# SwitchBoard_1_1.net
KiCad netlist of a schematic drawn in EAGLE
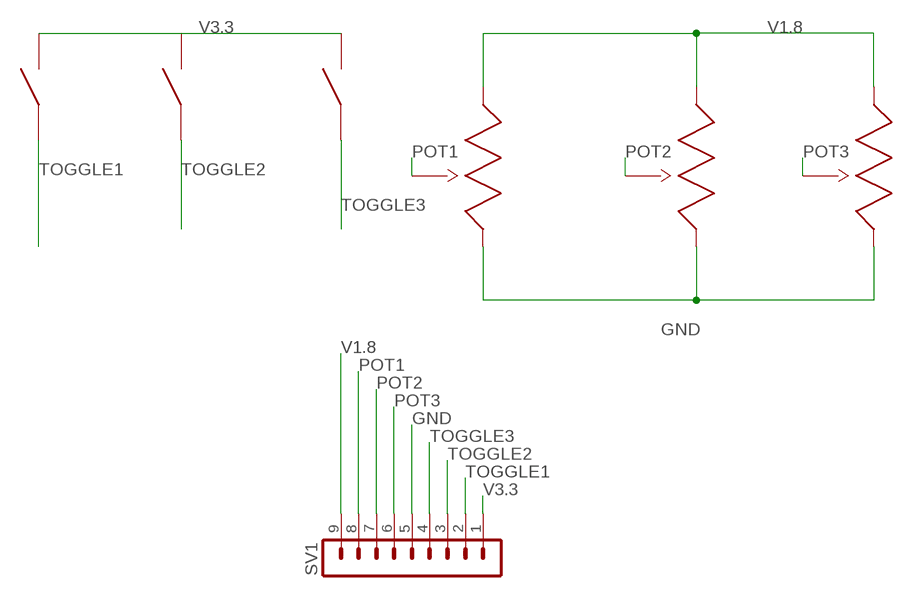
[diagram p0: schematic, sheet 1]

(export (version "E")
  (design (tool "Eeschema 10.0.6"))
  (components
    (comp (ref "POT1")
      (value "PRS11S-11")
      (footprint "eagle-import:POT-SMD")
      (libsource (lib "eagle-import") (part "PRS11S-11"))
    )
    (comp (ref "POT2")
      (value "PRS11S-11")
      (footprint "eagle-import:POT-SMD")
      (libsource (lib "eagle-import") (part "PRS11S-11"))
    )
    (comp (ref "POT3")
      (value "PRS11S-11")
      (footprint "eagle-import:POT-SMD")
      (libsource (lib "eagle-import") (part "PRS11S-11"))
    )
    (comp (ref "SV1")
      (value "MA09-1")
      (footprint "eagle-import:MA09-1")
      (libsource (lib "eagle-import") (part "MA09-1"))
    )
    (comp (ref "TOGGLE1")
      (value "COM-09276")
      (footprint "eagle-import:SPST-TOGGLE-SWITCH")
      (libsource (lib "eagle-import") (part "COM-09276"))
    )
    (comp (ref "TOGGLE2")
      (value "COM-09276")
      (footprint "eagle-import:SPST-TOGGLE-SWITCH")
      (libsource (lib "eagle-import") (part "COM-09276"))
    )
    (comp (ref "TOGGLE3")
      (value "COM-09276")
      (footprint "eagle-import:SPST-TOGGLE-SWITCH")
      (libsource (lib "eagle-import") (part "COM-09276"))
    )
  )
  (nets
    (net (code "1") (name "/GND") (class "Default")
      (node (ref "POT1") (pin "1") (pinfunction "1_1") (pintype "bidirectional"))
      (node (ref "POT2") (pin "1") (pinfunction "1_1") (pintype "bidirectional"))
      (node (ref "POT3") (pin "1") (pinfunction "1_1") (pintype "bidirectional"))
      (node (ref "SV1") (pin "5") (pinfunction "5_5") (pintype "passive"))
    )
    (net (code "2") (name "/POT1") (class "Default")
      (node (ref "POT1") (pin "2") (pinfunction "2_2") (pintype "bidirectional"))
      (node (ref "SV1") (pin "8") (pinfunction "8_8") (pintype "passive"))
    )
    (net (code "3") (name "/POT2") (class "Default")
      (node (ref "POT2") (pin "2") (pinfunction "2_2") (pintype "bidirectional"))
      (node (ref "SV1") (pin "7") (pinfunction "7_7") (pintype "passive"))
    )
    (net (code "4") (name "/POT3") (class "Default")
      (node (ref "POT3") (pin "2") (pinfunction "2_2") (pintype "bidirectional"))
      (node (ref "SV1") (pin "6") (pinfunction "6_6") (pintype "passive"))
    )
    (net (code "5") (name "/TOGGLE1") (class "Default")
      (node (ref "SV1") (pin "2") (pinfunction "2_2") (pintype "passive"))
      (node (ref "TOGGLE1") (pin "1") (pinfunction "1_1") (pintype "bidirectional"))
    )
    (net (code "6") (name "/TOGGLE2") (class "Default")
      (node (ref "SV1") (pin "3") (pinfunction "3_3") (pintype "passive"))
      (node (ref "TOGGLE2") (pin "1") (pinfunction "1_1") (pintype "bidirectional"))
    )
    (net (code "7") (name "/TOGGLE3") (class "Default")
      (node (ref "SV1") (pin "4") (pinfunction "4_4") (pintype "passive"))
      (node (ref "TOGGLE3") (pin "1") (pinfunction "1_1") (pintype "bidirectional"))
    )
    (net (code "8") (name "/V1.8") (class "Default")
      (node (ref "POT1") (pin "3") (pinfunction "3_3") (pintype "bidirectional"))
      (node (ref "POT2") (pin "3") (pinfunction "3_3") (pintype "bidirectional"))
      (node (ref "POT3") (pin "3") (pinfunction "3_3") (pintype "bidirectional"))
      (node (ref "SV1") (pin "9") (pinfunction "9_9") (pintype "passive"))
    )
    (net (code "9") (name "/V3.3") (class "Default")
      (node (ref "SV1") (pin "1") (pinfunction "1_1") (pintype "passive"))
      (node (ref "TOGGLE1") (pin "2") (pinfunction "2_2") (pintype "bidirectional"))
      (node (ref "TOGGLE2") (pin "2") (pinfunction "2_2") (pintype "bidirectional"))
      (node (ref "TOGGLE3") (pin "2") (pinfunction "2_2") (pintype "bidirectional"))
    )
  )
)
